# adapter.net
KiCad netlist of a schematic drawn in EAGLE
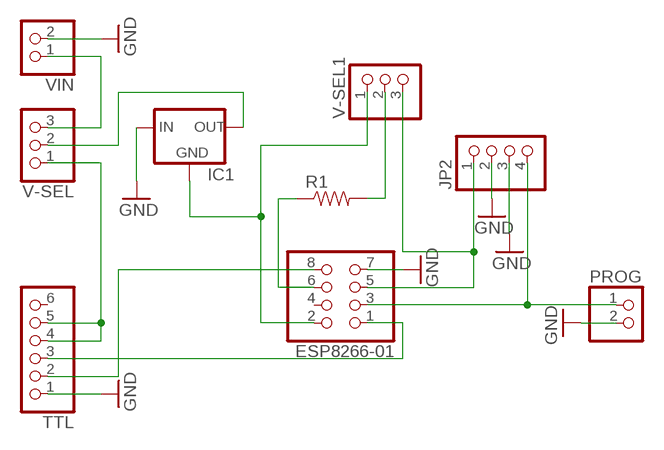
[diagram p0: schematic, sheet 1]

(export (version "E")
  (design (tool "Eeschema 10.0.6"))
  (components
    (comp (ref "ESP8266-01")
      (value "PINHD-2X4")
      (footprint "eagle-import:2X04")
      (libsource (lib "eagle-import") (part "PINHD-2X4"))
    )
    (comp (ref "IC1")
      (value "V_REG_78XXSIDE")
      (footprint "eagle-import:78XXL")
      (libsource (lib "eagle-import") (part "V_REG_78XXSIDE"))
    )
    (comp (ref "JP2")
      (value "PINHD-1X4")
      (footprint "eagle-import:1X04")
      (libsource (lib "eagle-import") (part "PINHD-1X4"))
    )
    (comp (ref "PROG")
      (value "PINHD-1X2")
      (footprint "eagle-import:1X02")
      (libsource (lib "eagle-import") (part "PINHD-1X2"))
    )
    (comp (ref "R1")
      (value "RESISTORAXIAL-0.3")
      (footprint "eagle-import:AXIAL-0.3")
      (libsource (lib "eagle-import") (part "RESISTORAXIAL-0.3"))
    )
    (comp (ref "TTL")
      (value "PINHD-1X6")
      (footprint "eagle-import:1X06")
      (libsource (lib "eagle-import") (part "PINHD-1X6"))
    )
    (comp (ref "V-SEL")
      (value "PINHD-1X3")
      (footprint "eagle-import:1X03")
      (libsource (lib "eagle-import") (part "PINHD-1X3"))
    )
    (comp (ref "V-SEL1")
      (value "PINHD-1X3")
      (footprint "eagle-import:1X03")
      (libsource (lib "eagle-import") (part "PINHD-1X3"))
    )
    (comp (ref "VIN")
      (value "PINHD-1X2")
      (footprint "eagle-import:1X02")
      (libsource (lib "eagle-import") (part "PINHD-1X2"))
    )
  )
  (nets
    (net (code "1") (name "GND") (class "Default")
      (node (ref "ESP8266-01") (pin "7") (pinfunction "7_7") (pintype "passive"))
      (node (ref "IC1") (pin "IN") (pinfunction "IN_IN") (pintype "input"))
      (node (ref "JP2") (pin "2") (pinfunction "2_2") (pintype "passive"))
      (node (ref "JP2") (pin "3") (pinfunction "3_3") (pintype "passive"))
      (node (ref "PROG") (pin "2") (pinfunction "2_2") (pintype "passive"))
      (node (ref "TTL") (pin "1") (pinfunction "1_1") (pintype "passive"))
      (node (ref "VIN") (pin "2") (pinfunction "2_2") (pintype "passive"))
    )
    (net (code "2") (name "Net-(ESP8266-01-Pad1)") (class "Default")
      (node (ref "ESP8266-01") (pin "1") (pinfunction "1_1") (pintype "passive"))
      (node (ref "TTL") (pin "3") (pinfunction "3_3") (pintype "passive"))
    )
    (net (code "3") (name "Net-(ESP8266-01-Pad2)") (class "Default")
      (node (ref "ESP8266-01") (pin "2") (pinfunction "2_2") (pintype "passive"))
      (node (ref "IC1") (pin "GND") (pinfunction "GND_GND") (pintype "input"))
      (node (ref "V-SEL1") (pin "1") (pinfunction "1_1") (pintype "passive"))
    )
    (net (code "4") (name "Net-(ESP8266-01-Pad3)") (class "Default")
      (node (ref "ESP8266-01") (pin "3") (pinfunction "3_3") (pintype "passive"))
      (node (ref "JP2") (pin "4") (pinfunction "4_4") (pintype "passive"))
      (node (ref "PROG") (pin "1") (pinfunction "1_1") (pintype "passive"))
    )
    (net (code "5") (name "Net-(ESP8266-01-Pad5)") (class "Default")
      (node (ref "ESP8266-01") (pin "5") (pinfunction "5_5") (pintype "passive"))
      (node (ref "JP2") (pin "1") (pinfunction "1_1") (pintype "passive"))
      (node (ref "V-SEL1") (pin "3") (pinfunction "3_3") (pintype "passive"))
    )
    (net (code "6") (name "Net-(ESP8266-01-Pad8)") (class "Default")
      (node (ref "ESP8266-01") (pin "8") (pinfunction "8_8") (pintype "passive"))
      (node (ref "TTL") (pin "2") (pinfunction "2_2") (pintype "passive"))
    )
    (net (code "7") (name "Net-(IC1-PadOUT)") (class "Default")
      (node (ref "IC1") (pin "OUT") (pinfunction "OUT_OUT") (pintype "output"))
      (node (ref "V-SEL") (pin "2") (pinfunction "2_2") (pintype "passive"))
    )
    (net (code "8") (name "Net-(R1-1)") (class "Default")
      (node (ref "ESP8266-01") (pin "6") (pinfunction "6_6") (pintype "passive"))
      (node (ref "R1") (pin "P$1") (pinfunction "1_P$1") (pintype "passive"))
    )
    (net (code "9") (name "Net-(R1-2)") (class "Default")
      (node (ref "R1") (pin "P$2") (pinfunction "2_P$2") (pintype "passive"))
      (node (ref "V-SEL1") (pin "2") (pinfunction "2_2") (pintype "passive"))
    )
    (net (code "10") (name "Net-(TTL-Pad4)") (class "Default")
      (node (ref "TTL") (pin "4") (pinfunction "4_4") (pintype "passive"))
      (node (ref "TTL") (pin "5") (pinfunction "5_5") (pintype "passive"))
      (node (ref "V-SEL") (pin "1") (pinfunction "1_1") (pintype "passive"))
    )
    (net (code "11") (name "Net-(V-SEL-Pad3)") (class "Default")
      (node (ref "V-SEL") (pin "3") (pinfunction "3_3") (pintype "passive"))
      (node (ref "VIN") (pin "1") (pinfunction "1_1") (pintype "passive"))
    )
    (net (code "12") (name "unconnected-(ESP8266-01-Pad4)") (class "Default")
      (node (ref "ESP8266-01") (pin "4") (pinfunction "4_4") (pintype "passive"))
    )
    (net (code "13") (name "unconnected-(TTL-Pad6)") (class "Default")
      (node (ref "TTL") (pin "6") (pinfunction "6_6") (pintype "passive"))
    )
  )
)
